# 2d_list_2.net
KiCad netlist of a schematic drawn in Altium Designer
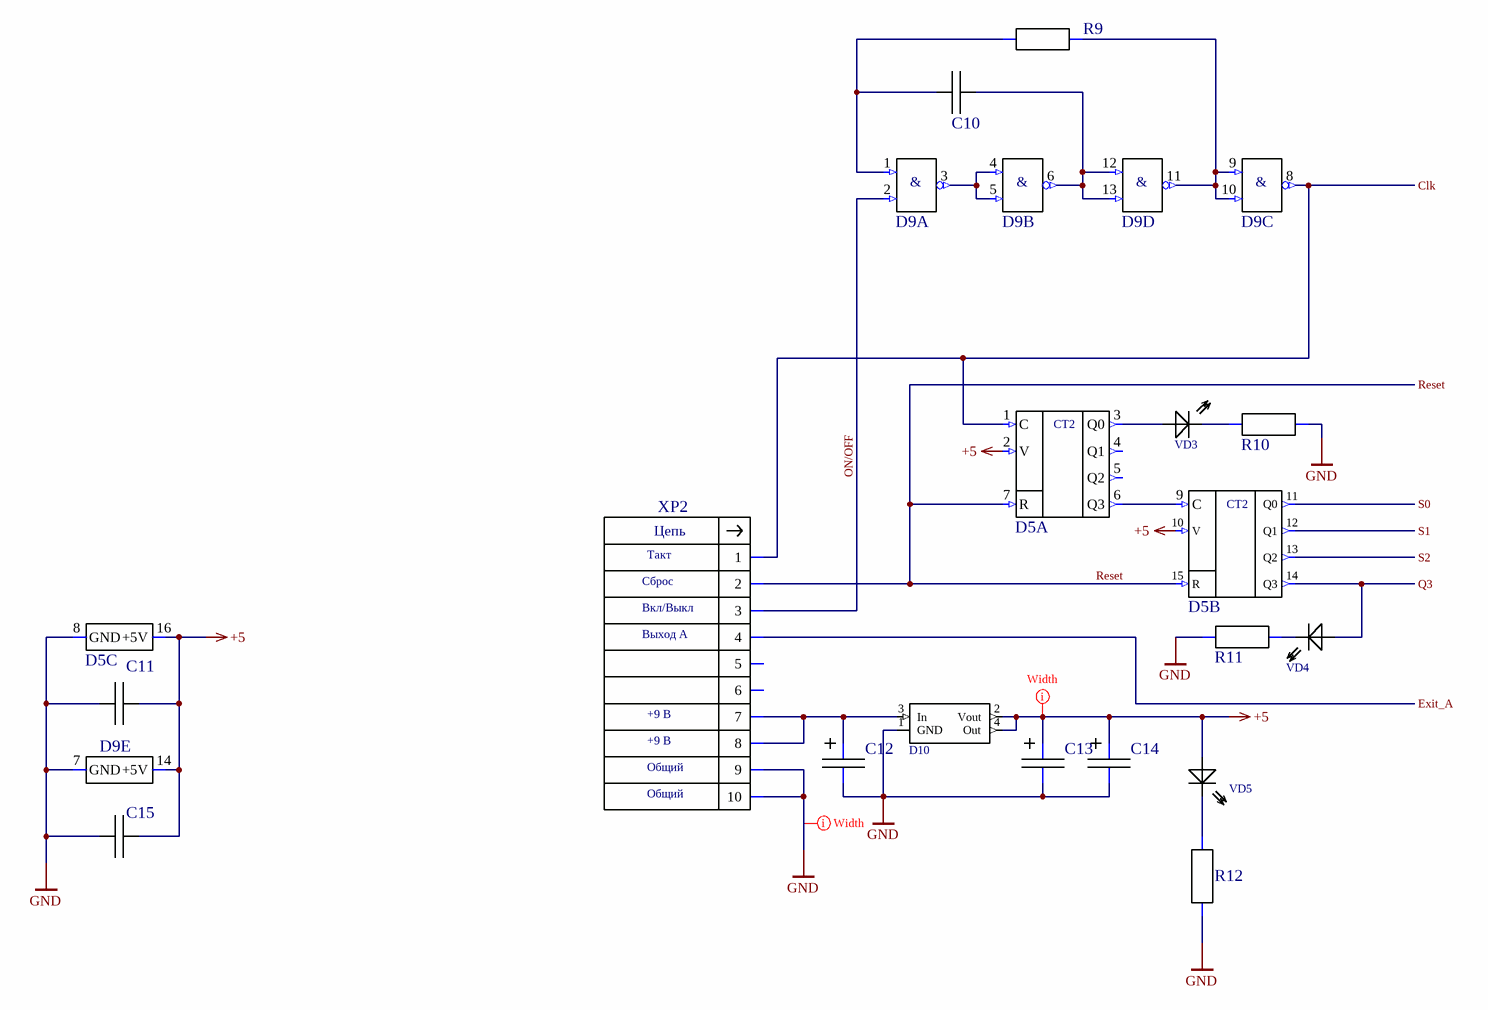
[diagram p0: 2d_list_2.schdoc]

(export (version "E")
  (design (tool "Eeschema 10.0.6"))
  (components
    (comp (ref "C10")
      (value "3224 (8х6мм)")
      (footprint "K10-79_8_6(3224)")
      (description "Чип конденсатор 3224 МП0 ряд Е24")
      (fields (field (name "MANUFACTURER") "ООО \"Кулон\"") (field (name "TOLERANCE") "±5%"))
      (libsource (lib "Int_Library_for_Lessons_3") (part "К10-79_3224_МП0"))
    )
    (comp (ref "C11")
      (value "1206")
      (footprint "K10-79_3.2_1.6(1206)")
      (description "Чип конденсатор 1206 Н90 ряд Е6")
      (fields (field (name "MANUFACTURER") "ООО \"Кулон\"") (field (name "TOLERANCE") "+80%-20%"))
      (libsource (lib "Int_Library_for_Lessons_3") (part "К10-79_1206_Н90"))
    )
    (comp (ref "C12")
      (value "C")
      (footprint "C-Tantal")
      (description "К53-65 Конденсатор танталовый C(6032) 0,47-100 мкФ")
      (fields
        (field (name "MANUFACTURER") "ОАО \"Элеконд\"")
        (field (name "TOLERANCE") "10%")
        (field (name "CREATED_BY") "Желобаев")
      )
      (libsource (lib "Int_Library_for_Lessons_3") (part "K53-65_C_10%"))
    )
    (comp (ref "C13")
      (value "C")
      (footprint "C-Tantal")
      (description "К53-65 Конденсатор танталовый C(6032) 0,47-100 мкФ")
      (fields
        (field (name "MANUFACTURER") "ОАО \"Элеконд\"")
        (field (name "TOLERANCE") "10%")
        (field (name "CREATED_BY") "Желобаев")
      )
      (libsource (lib "Int_Library_for_Lessons_3") (part "K53-65_C_10%"))
    )
    (comp (ref "C14")
      (value "C")
      (footprint "C-Tantal")
      (description "К53-65 Конденсатор танталовый C(6032) 0,47-100 мкФ")
      (fields
        (field (name "MANUFACTURER") "ОАО \"Элеконд\"")
        (field (name "TOLERANCE") "10%")
        (field (name "CREATED_BY") "Желобаев")
      )
      (libsource (lib "Int_Library_for_Lessons_3") (part "K53-65_C_10%"))
    )
    (comp (ref "C15")
      (value "1206")
      (footprint "K10-79_3.2_1.6(1206)")
      (description "Чип конденсатор 1206 Н90 ряд Е6")
      (fields (field (name "MANUFACTURER") "ООО \"Кулон\"") (field (name "TOLERANCE") "+80%-20%"))
      (libsource (lib "Int_Library_for_Lessons_3") (part "К10-79_1206_Н90"))
    )
    (comp (ref "D5")
      (value "~")
      (footprint "DIP16")
      (description "Два двоичных счетчика")
      (fields (field (name "MANUFACTURER") "Motorola") (field (name "CREATED_BY") "Желобаев"))
      (libsource (lib "Int_Library_for_Lessons_3") (part "MC14520BCP"))
    )
    (comp (ref "D9")
      (value "74AC00PC")
      (footprint "DIP14")
      (description "4 элемента 2И-НЕ TTL PDIP-14")
      (fields (field (name "MANUFACTURER") "ON Semiconductor") (field (name "CREATED_BY") "Желобаев"))
      (libsource (lib "Int_Library_for_Lessons_3") (part "74AC00PC"))
    )
    (comp (ref "D10")
      (value "Микросхема")
      (footprint "SOT230P700X180-4N")
      (libsource (lib "Schlib1") (part "LM1117IMP-5.0/NOPB"))
    )
    (comp (ref "R9")
      (value "~")
      (footprint "RES_1206_3216_N")
      (description "Резистор от 0,75 Ом до 2,2 МОм")
      (fields
        (field (name "MANUFACTURER") "ОАО \"НПО \"Эркон\"")
        (field (name "TOLERANCE") "5%")
        (field (name "CREATED_BY") "Желобаев")
      )
      (libsource (lib "Int_Library_for_Lessons_3") (part "Р1-12-0,25-5%"))
    )
    (comp (ref "R10")
      (value "~")
      (footprint "RES_0603_1608_N")
      (description "Резистор от 0,75 Ом до 10 МОм")
      (fields
        (field (name "MANUFACTURER") "ОАО \"НПО \"Эркон\"")
        (field (name "TOLERANCE") "5%")
        (field (name "CREATED_BY") "Желобаев")
      )
      (libsource (lib "Int_Library_for_Lessons_3") (part "Р1-12-0,1-5%"))
    )
    (comp (ref "R11")
      (value "~")
      (footprint "RES_0603_1608_N")
      (description "Резистор от 0,75 Ом до 10 МОм")
      (fields
        (field (name "MANUFACTURER") "ОАО \"НПО \"Эркон\"")
        (field (name "TOLERANCE") "5%")
        (field (name "CREATED_BY") "Желобаев")
      )
      (libsource (lib "Int_Library_for_Lessons_3") (part "Р1-12-0,1-5%"))
    )
    (comp (ref "R12")
      (value "~")
      (footprint "RES_0603_1608_N")
      (description "Резистор от 0,75 Ом до 10 МОм")
      (fields
        (field (name "MANUFACTURER") "ОАО \"НПО \"Эркон\"")
        (field (name "TOLERANCE") "5%")
        (field (name "CREATED_BY") "Желобаев")
      )
      (libsource (lib "Int_Library_for_Lessons_3") (part "Р1-12-0,1-5%"))
    )
    (comp (ref "VD3")
      (value "светодиод")
      (footprint "PcbLib1:521-9466")
      (libsource (lib "Schlib1") (part "521-9466"))
    )
    (comp (ref "VD4")
      (value "светодиод")
      (footprint "PcbLib1:521-9466")
      (libsource (lib "Schlib1") (part "521-9466"))
    )
    (comp (ref "VD5")
      (value "светодиод")
      (footprint "PcbLib1:521-9466")
      (libsource (lib "Schlib1") (part "521-9466"))
    )
    (comp (ref "XP2")
      (value "TE_1-1634689-0")
      (footprint "BH-10R")
      (description "Вилка типа BH-10R угловая правая двухрядная 2х5х2.54")
      (fields (field (name "MANUFACTURER") "TE Connectivity") (field (name "CREATED_BY") "Желобаев"))
      (libsource (lib "Int_Library_for_Lessons_3") (part "TE_1-1634689-0"))
    )
  )
  (nets
    (net (code "1") (name "+5") (class "Default")
      (node (ref "C11") (pin "2") (pinfunction "2_2") (pintype "passive"))
      (node (ref "C13") (pin "+") (pinfunction "+_+") (pintype "passive"))
      (node (ref "C14") (pin "+") (pinfunction "+_+") (pintype "passive"))
      (node (ref "C15") (pin "2") (pinfunction "2_2") (pintype "passive"))
      (node (ref "D10") (pin "2") (pinfunction "Vout_2") (pintype "output"))
      (node (ref "D10") (pin "4") (pinfunction "Out_4") (pintype "output"))
      (node (ref "D5") (pin "10") (pinfunction "V_10") (pintype "input"))
      (node (ref "D5") (pin "16") (pinfunction "+5V_16") (pintype "power_in"))
      (node (ref "D5") (pin "2") (pinfunction "V_2") (pintype "input"))
      (node (ref "D9") (pin "14") (pinfunction "+5V_14") (pintype "power_in"))
      (node (ref "VD5") (pin "A") (pinfunction "A_A") (pintype "passive"))
    )
    (net (code "2") (name "/Clk") (class "Default")
      (node (ref "D5") (pin "1") (pinfunction "C_1") (pintype "input"))
      (node (ref "D9") (pin "8") (pinfunction "Out_8") (pintype "output"))
      (node (ref "XP2") (pin "1") (pinfunction "1_1") (pintype "passive"))
    )
    (net (code "3") (name "/Exit_A") (class "Default")
      (node (ref "XP2") (pin "4") (pinfunction "4_4") (pintype "passive"))
    )
    (net (code "4") (name "/ON{slash}OFF") (class "Default")
      (node (ref "D9") (pin "2") (pinfunction "In2_2") (pintype "input"))
      (node (ref "XP2") (pin "3") (pinfunction "3_3") (pintype "passive"))
    )
    (net (code "5") (name "/Q3") (class "Default")
      (node (ref "D5") (pin "14") (pinfunction "Q3_14") (pintype "output"))
      (node (ref "VD4") (pin "A") (pinfunction "A_A") (pintype "passive"))
    )
    (net (code "6") (name "/Reset") (class "Default")
      (node (ref "D5") (pin "15") (pinfunction "R_15") (pintype "input"))
      (node (ref "D5") (pin "7") (pinfunction "R_7") (pintype "input"))
      (node (ref "XP2") (pin "2") (pinfunction "2_2") (pintype "passive"))
    )
    (net (code "7") (name "/S0") (class "Default")
      (node (ref "D5") (pin "11") (pinfunction "Q0_11") (pintype "output"))
    )
    (net (code "8") (name "/S1") (class "Default")
      (node (ref "D5") (pin "12") (pinfunction "Q1_12") (pintype "output"))
    )
    (net (code "9") (name "/S2") (class "Default")
      (node (ref "D5") (pin "13") (pinfunction "Q2_13") (pintype "output"))
    )
    (net (code "10") (name "GND") (class "Default")
      (node (ref "C11") (pin "1") (pinfunction "1_1") (pintype "passive"))
      (node (ref "C12") (pin "-") (pinfunction "-_-") (pintype "passive"))
      (node (ref "C13") (pin "-") (pinfunction "-_-") (pintype "passive"))
      (node (ref "C14") (pin "-") (pinfunction "-_-") (pintype "passive"))
      (node (ref "C15") (pin "1") (pinfunction "1_1") (pintype "passive"))
      (node (ref "D10") (pin "1") (pinfunction "GND_1") (pintype "power_in"))
      (node (ref "D5") (pin "8") (pinfunction "GND_8") (pintype "power_in"))
      (node (ref "D9") (pin "7") (pinfunction "GND_7") (pintype "power_in"))
      (node (ref "R10") (pin "2") (pinfunction "2_2") (pintype "passive"))
      (node (ref "R11") (pin "1") (pinfunction "1_1") (pintype "passive"))
      (node (ref "R12") (pin "1") (pinfunction "1_1") (pintype "passive"))
      (node (ref "XP2") (pin "10") (pinfunction "10_10") (pintype "passive"))
      (node (ref "XP2") (pin "9") (pinfunction "9_9") (pintype "passive"))
    )
    (net (code "11") (name "Net-(D5A-Q0)") (class "Default")
      (node (ref "D5") (pin "3") (pinfunction "Q0_3") (pintype "output"))
      (node (ref "VD3") (pin "A") (pinfunction "A_A") (pintype "passive"))
    )
    (net (code "12") (name "Net-(D5A-Q3)") (class "Default")
      (node (ref "D5") (pin "6") (pinfunction "Q3_6") (pintype "output"))
      (node (ref "D5") (pin "9") (pinfunction "C_9") (pintype "input"))
    )
    (net (code "13") (name "Net-(D9A-In1)") (class "Default")
      (node (ref "C10") (pin "1") (pinfunction "1_1") (pintype "passive"))
      (node (ref "D9") (pin "1") (pinfunction "In1_1") (pintype "input"))
      (node (ref "R9") (pin "1") (pinfunction "1_1") (pintype "passive"))
    )
    (net (code "14") (name "Net-(D9A-Out)") (class "Default")
      (node (ref "D9") (pin "3") (pinfunction "Out_3") (pintype "output"))
      (node (ref "D9") (pin "4") (pinfunction "In1_4") (pintype "input"))
      (node (ref "D9") (pin "5") (pinfunction "In2_5") (pintype "input"))
    )
    (net (code "15") (name "Net-(D9B-Out)") (class "Default")
      (node (ref "C10") (pin "2") (pinfunction "2_2") (pintype "passive"))
      (node (ref "D9") (pin "12") (pinfunction "In1_12") (pintype "input"))
      (node (ref "D9") (pin "13") (pinfunction "In2_13") (pintype "input"))
      (node (ref "D9") (pin "6") (pinfunction "Out_6") (pintype "output"))
    )
    (net (code "16") (name "Net-(D9C-In1)") (class "Default")
      (node (ref "D9") (pin "10") (pinfunction "In2_10") (pintype "input"))
      (node (ref "D9") (pin "11") (pinfunction "Out_11") (pintype "output"))
      (node (ref "D9") (pin "9") (pinfunction "In1_9") (pintype "input"))
      (node (ref "R9") (pin "2") (pinfunction "2_2") (pintype "passive"))
    )
    (net (code "17") (name "Net-(D10-In)") (class "Default")
      (node (ref "C12") (pin "+") (pinfunction "+_+") (pintype "passive"))
      (node (ref "D10") (pin "3") (pinfunction "In_3") (pintype "input"))
      (node (ref "XP2") (pin "7") (pinfunction "7_7") (pintype "passive"))
      (node (ref "XP2") (pin "8") (pinfunction "8_8") (pintype "passive"))
    )
    (net (code "18") (name "Net-(R10-Pad1)") (class "Default")
      (node (ref "R10") (pin "1") (pinfunction "1_1") (pintype "passive"))
      (node (ref "VD3") (pin "KK") (pinfunction "KK_KK") (pintype "passive"))
    )
    (net (code "19") (name "Net-(R11-Pad2)") (class "Default")
      (node (ref "R11") (pin "2") (pinfunction "2_2") (pintype "passive"))
      (node (ref "VD4") (pin "KK") (pinfunction "KK_KK") (pintype "passive"))
    )
    (net (code "20") (name "Net-(R12-Pad2)") (class "Default")
      (node (ref "R12") (pin "2") (pinfunction "2_2") (pintype "passive"))
      (node (ref "VD5") (pin "KK") (pinfunction "KK_KK") (pintype "passive"))
    )
    (net (code "21") (name "unconnected-(D5A-Q1-Pad4)") (class "Default")
      (node (ref "D5") (pin "4") (pinfunction "Q1_4") (pintype "output"))
    )
    (net (code "22") (name "unconnected-(D5A-Q2-Pad5)") (class "Default")
      (node (ref "D5") (pin "5") (pinfunction "Q2_5") (pintype "output"))
    )
    (net (code "23") (name "unconnected-(XP2-Pad5)") (class "Default")
      (node (ref "XP2") (pin "5") (pinfunction "5_5") (pintype "passive"))
    )
    (net (code "24") (name "unconnected-(XP2-Pad6)") (class "Default")
      (node (ref "XP2") (pin "6") (pinfunction "6_6") (pintype "passive"))
    )
  )
)
